# sensor.net
KiCad netlist of a schematic drawn in Altium Designer
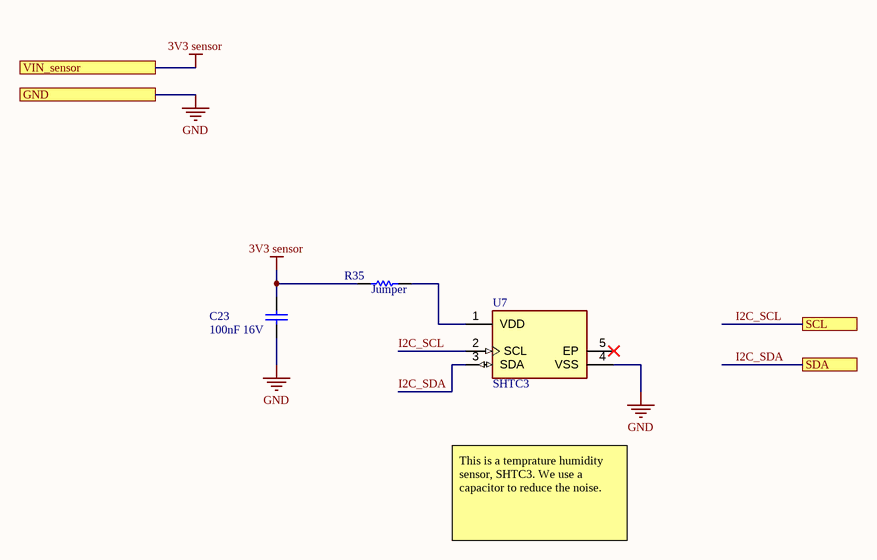
[diagram p0: sensor.SchDoc]

(export (version "E")
  (design (tool "Eeschema 10.0.6"))
  (components
    (comp (ref "C23")
      (value "100nF 16V")
      (footprint "CAPC0603(1608)100_N")
      (description "CAP 100nF 16V ±10% 0603 (1608 Metric) Thickness 1mm SMD")
      (fields (field (name "TOLERANCE") "Â±10%"))
      (libsource (lib "Altium Content Vault") (part "CAP"))
    )
    (comp (ref "R35")
      (value "Jumper")
      (footprint "RESC0603(1608)_N")
      (description "Jumper 0603 (1608 Metric)")
      (fields (field (name "POWER") "None"))
      (libsource (lib "Altium Content Vault") (part "RES"))
    )
    (comp (ref "U7")
      (value "SHTC3")
      (footprint "FP-SHTC3-IPC_A")
      (description "SENSOR HUMI/TEMP I2C 2% SMD")
      (fields
        (field (name "MANUFACTURER") "Sensirion")
        (field (name "OCTOPART") "https://octopart.com/shtc3-sensirion-91912225")
      )
      (libsource (lib "Sensor") (part "CMP-144040-000003-1"))
    )
  )
  (nets
    (net (code "1") (name "/I2C_SCL") (class "Default")
      (node (ref "U7") (pin "2") (pinfunction "SCL_2") (pintype "input"))
    )
    (net (code "2") (name "/I2C_SDA") (class "Default")
      (node (ref "U7") (pin "3") (pinfunction "SDA_3") (pintype "bidirectional"))
    )
    (net (code "3") (name "3V3 sensor") (class "Default")
      (node (ref "C23") (pin "2") (pinfunction "2_2") (pintype "passive"))
      (node (ref "R35") (pin "1") (pinfunction "1_1") (pintype "passive"))
    )
    (net (code "4") (name "GND") (class "Default")
      (node (ref "C23") (pin "1") (pinfunction "1_1") (pintype "passive"))
      (node (ref "U7") (pin "4") (pinfunction "VSS_4") (pintype "power_in"))
    )
    (net (code "5") (name "Net-(U7-VDD)") (class "Default")
      (node (ref "R35") (pin "2") (pinfunction "2_2") (pintype "passive"))
      (node (ref "U7") (pin "1") (pinfunction "VDD_1") (pintype "power_in"))
    )
    (net (code "6") (name "unconnected-(U7-EP-Pad5)") (class "Default")
      (node (ref "U7") (pin "5") (pinfunction "EP_5") (pintype "power_in+no_connect"))
    )
  )
)
